# MPU6050-IMU_I2C_V2.net
KiCad netlist of a schematic drawn in EAGLE
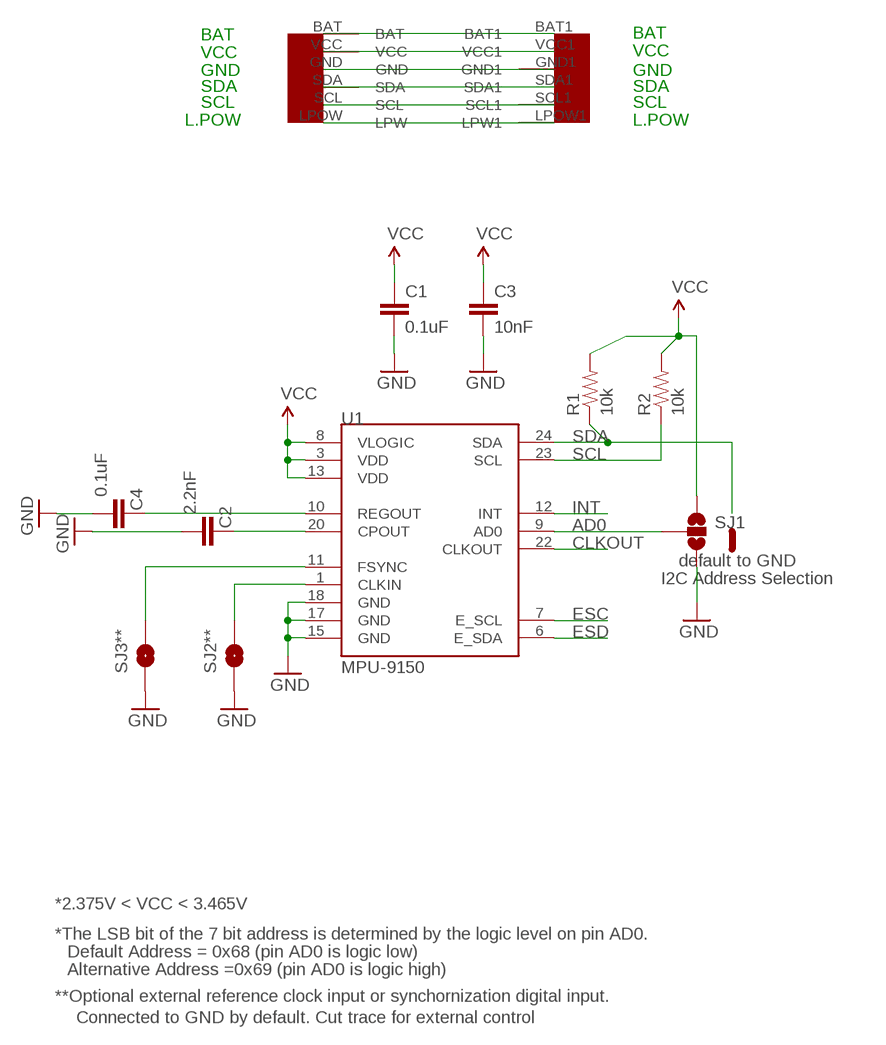
[diagram p0: schematic, sheet 1]

(export (version "E")
  (design (tool "Eeschema 10.0.6"))
  (components
    (comp (ref "C1")
      (value "0.1uF")
      (footprint "eagle-import:0402-CAP")
      (fields (field (name "MF") "AVX") (field (name "MPN") "02016D104KAT2A"))
      (libsource (lib "eagle-import") (part "CAP0402-CAP"))
    )
    (comp (ref "C2")
      (value "2.2nF")
      (footprint "eagle-import:0402-CAP")
      (fields (field (name "MF") "AVX") (field (name "MPN") "06035C222KAT2A"))
      (libsource (lib "eagle-import") (part "CAP0402-CAP"))
    )
    (comp (ref "C3")
      (value "10nF")
      (footprint "eagle-import:0402-CAP")
      (fields (field (name "MF") "AVX") (field (name "MPN") "06035G103ZAT2A"))
      (libsource (lib "eagle-import") (part "CAP0402-CAP"))
    )
    (comp (ref "C4")
      (value "0.1uF")
      (footprint "eagle-import:0402-CAP")
      (fields (field (name "MF") "AVX") (field (name "MPN") "02016D104KAT2A"))
      (libsource (lib "eagle-import") (part "CAP0402-CAP"))
    )
    (comp (ref "R1")
      (value "10k")
      (footprint "eagle-import:0402-RES")
      (libsource (lib "eagle-import") (part "RESISTOR0402-RES"))
    )
    (comp (ref "R2")
      (value "10k")
      (footprint "eagle-import:0402-RES")
      (libsource (lib "eagle-import") (part "RESISTOR0402-RES"))
    )
    (comp (ref "SJ1")
      (value "SOLDERJUMPER_2WAYPASTE2&3")
      (footprint "eagle-import:SJ_3_PASTE2&3")
      (libsource (lib "eagle-import") (part "SOLDERJUMPER_2WAYPASTE2&3"))
    )
    (comp (ref "SJ2**")
      (value "SOLDERJUMPERTRACE")
      (footprint "eagle-import:SJ_2S-TRACE")
      (libsource (lib "eagle-import") (part "SOLDERJUMPERTRACE"))
    )
    (comp (ref "SJ3**")
      (value "SOLDERJUMPERTRACE")
      (footprint "eagle-import:SJ_2S-TRACE")
      (libsource (lib "eagle-import") (part "SOLDERJUMPERTRACE"))
    )
    (comp (ref "U$1")
      (value "EZ-I2CHEADERV1")
      (footprint "eagle-import:EZ-I2CHEADERV1")
      (libsource (lib "eagle-import") (part "EZ-I2CHEADERV1"))
    )
    (comp (ref "U1")
      (value "MPU-9150")
      (footprint "eagle-import:QFN-24-NP")
      (libsource (lib "eagle-import") (part "MPU-9150QFN-24-NP"))
    )
  )
  (nets
    (net (code "1") (name "/AD0") (class "Default")
      (node (ref "SJ1") (pin "2") (pinfunction "2_2") (pintype "passive"))
      (node (ref "U1") (pin "9") (pinfunction "AD0_9") (pintype "bidirectional"))
    )
    (net (code "2") (name "/CLKOUT") (class "Default")
      (node (ref "U1") (pin "22") (pinfunction "CLKOUT_22") (pintype "bidirectional"))
    )
    (net (code "3") (name "/ESC") (class "Default")
      (node (ref "U1") (pin "7") (pinfunction "E_SCL_7") (pintype "bidirectional"))
    )
    (net (code "4") (name "/ESD") (class "Default")
      (node (ref "U1") (pin "6") (pinfunction "E_SDA_6") (pintype "bidirectional"))
    )
    (net (code "5") (name "/INT") (class "Default")
      (node (ref "U1") (pin "12") (pinfunction "INT_12") (pintype "bidirectional"))
    )
    (net (code "6") (name "/SCL") (class "Default")
      (node (ref "R2") (pin "1") (pinfunction "1_1") (pintype "passive"))
      (node (ref "U$1") (pin "SCL") (pinfunction "SCL_SCL") (pintype "bidirectional"))
      (node (ref "U$1") (pin "SCL1") (pinfunction "SCL1_SCL1") (pintype "bidirectional"))
      (node (ref "U1") (pin "23") (pinfunction "SCL_23") (pintype "bidirectional"))
    )
    (net (code "7") (name "/SDA") (class "Default")
      (node (ref "R1") (pin "1") (pinfunction "1_1") (pintype "passive"))
      (node (ref "U$1") (pin "SDA") (pinfunction "SDA_SDA") (pintype "bidirectional"))
      (node (ref "U$1") (pin "SDA1") (pinfunction "SDA1_SDA1") (pintype "bidirectional"))
      (node (ref "U1") (pin "24") (pinfunction "SDA_24") (pintype "bidirectional"))
    )
    (net (code "8") (name "GND") (class "Default")
      (node (ref "C1") (pin "2") (pinfunction "2_2") (pintype "passive"))
      (node (ref "C2") (pin "2") (pinfunction "2_2") (pintype "passive"))
      (node (ref "C3") (pin "2") (pinfunction "2_2") (pintype "passive"))
      (node (ref "C4") (pin "2") (pinfunction "2_2") (pintype "passive"))
      (node (ref "SJ1") (pin "3") (pinfunction "3_3") (pintype "passive"))
      (node (ref "SJ2**") (pin "1") (pinfunction "1_1") (pintype "passive"))
      (node (ref "SJ3**") (pin "1") (pinfunction "1_1") (pintype "passive"))
      (node (ref "U$1") (pin "GND") (pinfunction "GND_GND") (pintype "bidirectional"))
      (node (ref "U$1") (pin "GND1") (pinfunction "GND1_GND1") (pintype "bidirectional"))
      (node (ref "U1") (pin "15") (pinfunction "GND_15") (pintype "bidirectional"))
      (node (ref "U1") (pin "17") (pinfunction "GND_17") (pintype "bidirectional"))
      (node (ref "U1") (pin "18") (pinfunction "GND_18") (pintype "bidirectional"))
    )
    (net (code "9") (name "Net-(U$1-LPW)") (class "Default")
      (node (ref "U$1") (pin "LPOW") (pinfunction "LPW_LPOW") (pintype "bidirectional"))
      (node (ref "U$1") (pin "LPOW1") (pinfunction "LPW1_LPOW1") (pintype "bidirectional"))
    )
    (net (code "10") (name "Net-(U$1-PadBAT)") (class "Default")
      (node (ref "U$1") (pin "BAT") (pinfunction "BAT_BAT") (pintype "bidirectional"))
      (node (ref "U$1") (pin "BAT1") (pinfunction "BAT1_BAT1") (pintype "bidirectional"))
    )
    (net (code "11") (name "Net-(U1-CLKIN)") (class "Default")
      (node (ref "SJ2**") (pin "2") (pinfunction "2_2") (pintype "passive"))
      (node (ref "U1") (pin "1") (pinfunction "CLKIN_1") (pintype "bidirectional"))
    )
    (net (code "12") (name "Net-(U1-CPOUT)") (class "Default")
      (node (ref "C2") (pin "1") (pinfunction "1_1") (pintype "passive"))
      (node (ref "U1") (pin "20") (pinfunction "CPOUT_20") (pintype "bidirectional"))
    )
    (net (code "13") (name "Net-(U1-FSYNC)") (class "Default")
      (node (ref "SJ3**") (pin "2") (pinfunction "2_2") (pintype "passive"))
      (node (ref "U1") (pin "11") (pinfunction "FSYNC_11") (pintype "bidirectional"))
    )
    (net (code "14") (name "Net-(U1-REGOUT)") (class "Default")
      (node (ref "C4") (pin "1") (pinfunction "1_1") (pintype "passive"))
      (node (ref "U1") (pin "10") (pinfunction "REGOUT_10") (pintype "bidirectional"))
    )
    (net (code "15") (name "VCC") (class "Default")
      (node (ref "C1") (pin "1") (pinfunction "1_1") (pintype "passive"))
      (node (ref "C3") (pin "1") (pinfunction "1_1") (pintype "passive"))
      (node (ref "R1") (pin "2") (pinfunction "2_2") (pintype "passive"))
      (node (ref "R2") (pin "2") (pinfunction "2_2") (pintype "passive"))
      (node (ref "SJ1") (pin "1") (pinfunction "1_1") (pintype "passive"))
      (node (ref "U$1") (pin "VCC") (pinfunction "VCC_VCC") (pintype "bidirectional"))
      (node (ref "U$1") (pin "VCC1") (pinfunction "VCC1_VCC1") (pintype "bidirectional"))
      (node (ref "U1") (pin "13") (pinfunction "VDD_13") (pintype "bidirectional"))
      (node (ref "U1") (pin "3") (pinfunction "VDD_3") (pintype "bidirectional"))
      (node (ref "U1") (pin "8") (pinfunction "VLOGIC_8") (pintype "bidirectional"))
    )
  )
)
